# model140.net
KiCad netlist of a schematic drawn in EAGLE
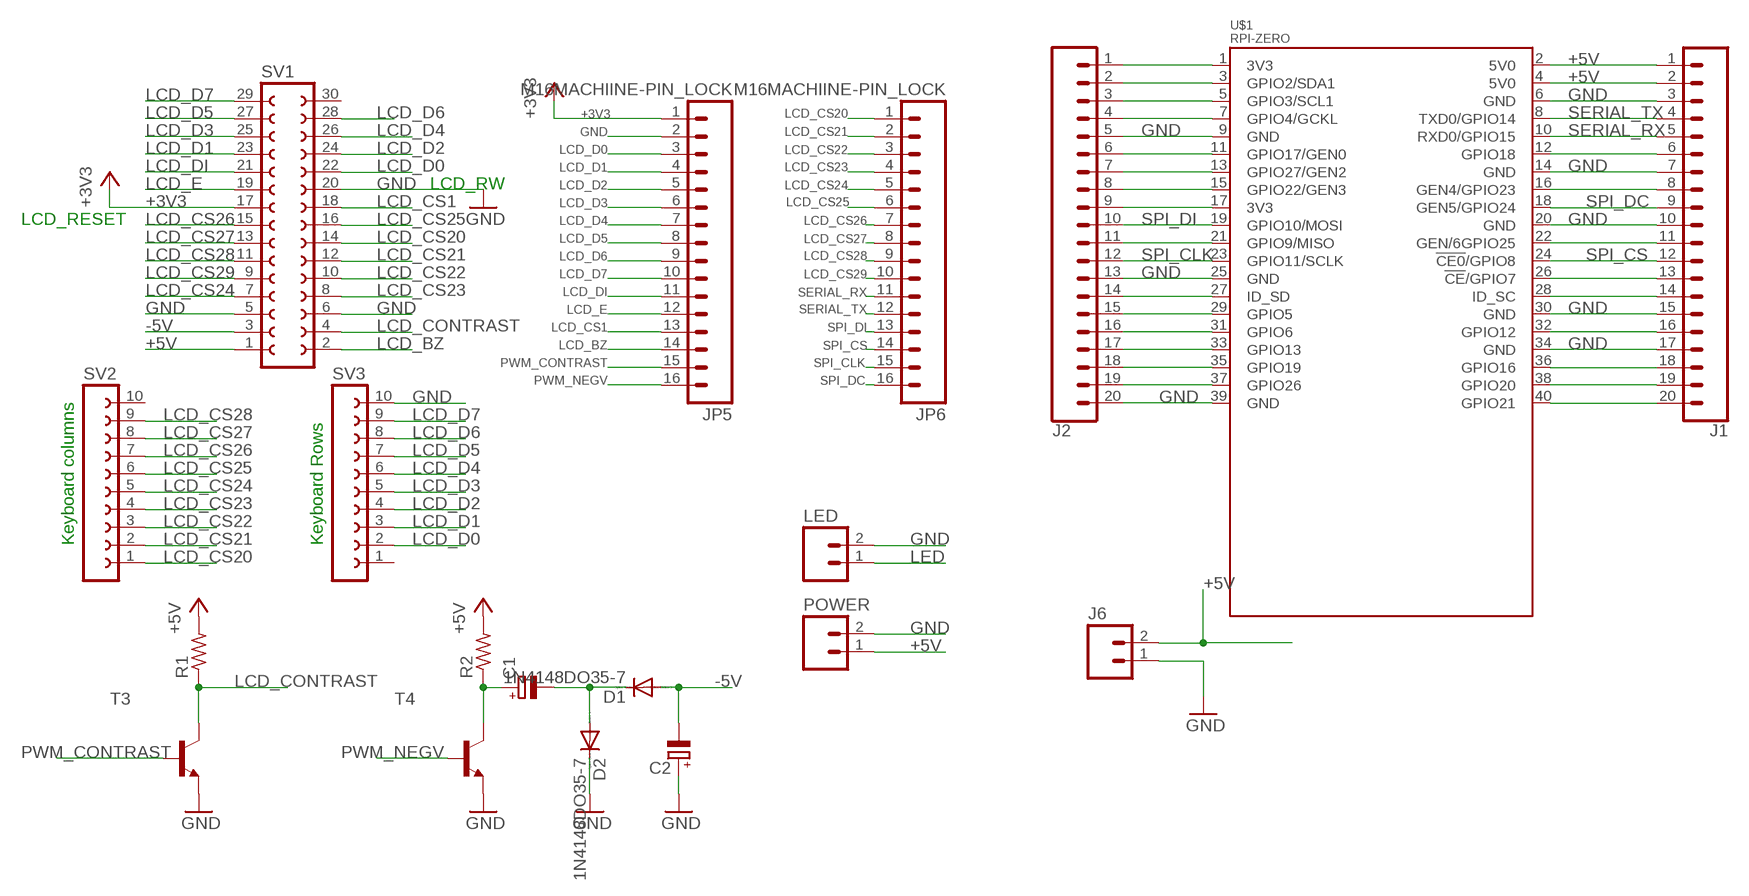
[diagram p0: schematic, sheet 1]

(export (version "E")
  (design (tool "Eeschema 10.0.6"))
  (components
    (comp (ref "C1")
      (value "CPOL-EUE2.5-7")
      (footprint "eagle-import:E2,5-7")
      (libsource (lib "eagle-import") (part "CPOL-EUE2.5-7"))
    )
    (comp (ref "C2")
      (value "CPOL-EUE2.5-7")
      (footprint "eagle-import:E2,5-7")
      (libsource (lib "eagle-import") (part "CPOL-EUE2.5-7"))
    )
    (comp (ref "D1")
      (value "1N4148DO35-7")
      (footprint "eagle-import:DO35-7")
      (libsource (lib "eagle-import") (part "1N4148DO35-7"))
    )
    (comp (ref "D2")
      (value "1N4148DO35-7")
      (footprint "eagle-import:DO35-7")
      (libsource (lib "eagle-import") (part "1N4148DO35-7"))
    )
    (comp (ref "J1")
      (value "CONN_20")
      (footprint "eagle-import:1X20")
      (libsource (lib "eagle-import") (part "CONN_20"))
    )
    (comp (ref "J2")
      (value "CONN_20")
      (footprint "eagle-import:1X20")
      (libsource (lib "eagle-import") (part "CONN_20"))
    )
    (comp (ref "J6")
      (value "M02PTH")
      (footprint "eagle-import:1X02")
      (libsource (lib "eagle-import") (part "M02PTH"))
    )
    (comp (ref "JP5")
      (value "M16MACHIINE-PIN_LOCK")
      (footprint "eagle-import:1X16_MACHINE-PIN-HEADER_LOCK.004@1")
      (libsource (lib "eagle-import") (part "M16MACHIINE-PIN_LOCK"))
    )
    (comp (ref "JP6")
      (value "M16MACHIINE-PIN_LOCK")
      (footprint "eagle-import:1X16_MACHINE-PIN-HEADER_LOCK.004@1")
      (libsource (lib "eagle-import") (part "M16MACHIINE-PIN_LOCK"))
    )
    (comp (ref "LED")
      (value "M02PTH")
      (footprint "eagle-import:1X02")
      (libsource (lib "eagle-import") (part "M02PTH"))
    )
    (comp (ref "POWER")
      (value "M02PTH")
      (footprint "eagle-import:1X02")
      (libsource (lib "eagle-import") (part "M02PTH"))
    )
    (comp (ref "R1")
      (value "R-US_0204/5")
      (footprint "eagle-import:0204_5")
      (libsource (lib "eagle-import") (part "R-US_0204/5"))
    )
    (comp (ref "R2")
      (value "R-US_0204/5")
      (footprint "eagle-import:0204_5")
      (libsource (lib "eagle-import") (part "R-US_0204/5"))
    )
    (comp (ref "SV1")
      (value "FE15-2")
      (footprint "eagle-import:FE15-2")
      (libsource (lib "eagle-import") (part "FE15-2"))
    )
    (comp (ref "SV2")
      (value "FE10W")
      (footprint "eagle-import:FE10W")
      (libsource (lib "eagle-import") (part "FE10W"))
    )
    (comp (ref "SV3")
      (value "FE10W")
      (footprint "eagle-import:FE10W")
      (libsource (lib "eagle-import") (part "FE10W"))
    )
    (comp (ref "T3")
      (value "MPS2222A-NPN-TO92-CBE")
      (footprint "eagle-import:TO92-CBE")
      (libsource (lib "eagle-import") (part "-NPN-TO92-CBEMPS2222A"))
    )
    (comp (ref "T4")
      (value "MPS2222A-NPN-TO92-CBE")
      (footprint "eagle-import:TO92-CBE")
      (libsource (lib "eagle-import") (part "-NPN-TO92-CBEMPS2222A"))
    )
    (comp (ref "U$1")
      (value "RPI-ZERO")
      (footprint "eagle-import:RASP_PI_ZERO_BOARD_FULL")
      (libsource (lib "eagle-import") (part "RPI-ZERO"))
    )
  )
  (nets
    (net (code "1") (name "+3V3") (class "Default")
      (node (ref "JP5") (pin "1") (pinfunction "1_1") (pintype "passive"))
      (node (ref "SV1") (pin "17") (pinfunction "17_17") (pintype "passive"))
    )
    (net (code "2") (name "+5V") (class "Default")
      (node (ref "J1") (pin "1") (pinfunction "1_1") (pintype "passive"))
      (node (ref "J1") (pin "2") (pinfunction "2_2") (pintype "passive"))
      (node (ref "J6") (pin "2") (pinfunction "2_2") (pintype "passive"))
      (node (ref "POWER") (pin "1") (pinfunction "1_1") (pintype "passive"))
      (node (ref "R1") (pin "2") (pinfunction "2_2") (pintype "passive"))
      (node (ref "R2") (pin "2") (pinfunction "2_2") (pintype "passive"))
      (node (ref "SV1") (pin "1") (pinfunction "1_1") (pintype "passive"))
      (node (ref "U$1") (pin "2") (pinfunction "5V0_2") (pintype "power_in"))
      (node (ref "U$1") (pin "4") (pinfunction "5V0_4") (pintype "power_in"))
    )
    (net (code "3") (name "/-5V") (class "Default")
      (node (ref "C2") (pin "-") (pinfunction "-_-") (pintype "passive"))
      (node (ref "D1") (pin "A") (pinfunction "A_A") (pintype "passive"))
      (node (ref "SV1") (pin "3") (pinfunction "3_3") (pintype "passive"))
    )
    (net (code "4") (name "/LCD_BZ") (class "Default")
      (node (ref "JP5") (pin "14") (pinfunction "14_14") (pintype "passive"))
      (node (ref "SV1") (pin "2") (pinfunction "2_2") (pintype "passive"))
    )
    (net (code "5") (name "/LCD_CONTRAST") (class "Default")
      (node (ref "R1") (pin "1") (pinfunction "1_1") (pintype "passive"))
      (node (ref "SV1") (pin "4") (pinfunction "4_4") (pintype "passive"))
      (node (ref "T3") (pin "C") (pinfunction "C_C") (pintype "passive"))
    )
    (net (code "6") (name "/LCD_CS1") (class "Default")
      (node (ref "JP5") (pin "13") (pinfunction "13_13") (pintype "passive"))
      (node (ref "SV1") (pin "18") (pinfunction "18_18") (pintype "passive"))
    )
    (net (code "7") (name "/LCD_CS20") (class "Default")
      (node (ref "JP6") (pin "1") (pinfunction "1_1") (pintype "passive"))
      (node (ref "SV1") (pin "14") (pinfunction "14_14") (pintype "passive"))
      (node (ref "SV2") (pin "1") (pinfunction "1_1") (pintype "passive"))
    )
    (net (code "8") (name "/LCD_CS21") (class "Default")
      (node (ref "JP6") (pin "2") (pinfunction "2_2") (pintype "passive"))
      (node (ref "SV1") (pin "12") (pinfunction "12_12") (pintype "passive"))
      (node (ref "SV2") (pin "2") (pinfunction "2_2") (pintype "passive"))
    )
    (net (code "9") (name "/LCD_CS22") (class "Default")
      (node (ref "JP6") (pin "3") (pinfunction "3_3") (pintype "passive"))
      (node (ref "SV1") (pin "10") (pinfunction "10_10") (pintype "passive"))
      (node (ref "SV2") (pin "3") (pinfunction "3_3") (pintype "passive"))
    )
    (net (code "10") (name "/LCD_CS23") (class "Default")
      (node (ref "JP6") (pin "4") (pinfunction "4_4") (pintype "passive"))
      (node (ref "SV1") (pin "8") (pinfunction "8_8") (pintype "passive"))
      (node (ref "SV2") (pin "4") (pinfunction "4_4") (pintype "passive"))
    )
    (net (code "11") (name "/LCD_CS24") (class "Default")
      (node (ref "JP6") (pin "5") (pinfunction "5_5") (pintype "passive"))
      (node (ref "SV1") (pin "7") (pinfunction "7_7") (pintype "passive"))
      (node (ref "SV2") (pin "5") (pinfunction "5_5") (pintype "passive"))
    )
    (net (code "12") (name "/LCD_CS25") (class "Default")
      (node (ref "JP6") (pin "6") (pinfunction "6_6") (pintype "passive"))
      (node (ref "SV1") (pin "16") (pinfunction "16_16") (pintype "passive"))
      (node (ref "SV2") (pin "6") (pinfunction "6_6") (pintype "passive"))
    )
    (net (code "13") (name "/LCD_CS26") (class "Default")
      (node (ref "JP6") (pin "7") (pinfunction "7_7") (pintype "passive"))
      (node (ref "SV1") (pin "15") (pinfunction "15_15") (pintype "passive"))
      (node (ref "SV2") (pin "7") (pinfunction "7_7") (pintype "passive"))
    )
    (net (code "14") (name "/LCD_CS27") (class "Default")
      (node (ref "JP6") (pin "8") (pinfunction "8_8") (pintype "passive"))
      (node (ref "SV1") (pin "13") (pinfunction "13_13") (pintype "passive"))
      (node (ref "SV2") (pin "8") (pinfunction "8_8") (pintype "passive"))
    )
    (net (code "15") (name "/LCD_CS28") (class "Default")
      (node (ref "JP6") (pin "9") (pinfunction "9_9") (pintype "passive"))
      (node (ref "SV1") (pin "11") (pinfunction "11_11") (pintype "passive"))
      (node (ref "SV2") (pin "9") (pinfunction "9_9") (pintype "passive"))
    )
    (net (code "16") (name "/LCD_CS29") (class "Default")
      (node (ref "JP6") (pin "10") (pinfunction "10_10") (pintype "passive"))
      (node (ref "SV1") (pin "9") (pinfunction "9_9") (pintype "passive"))
    )
    (net (code "17") (name "/LCD_D0") (class "Default")
      (node (ref "JP5") (pin "3") (pinfunction "3_3") (pintype "passive"))
      (node (ref "SV1") (pin "22") (pinfunction "22_22") (pintype "passive"))
      (node (ref "SV3") (pin "2") (pinfunction "2_2") (pintype "passive"))
    )
    (net (code "18") (name "/LCD_D1") (class "Default")
      (node (ref "JP5") (pin "4") (pinfunction "4_4") (pintype "passive"))
      (node (ref "SV1") (pin "23") (pinfunction "23_23") (pintype "passive"))
      (node (ref "SV3") (pin "3") (pinfunction "3_3") (pintype "passive"))
    )
    (net (code "19") (name "/LCD_D2") (class "Default")
      (node (ref "JP5") (pin "5") (pinfunction "5_5") (pintype "passive"))
      (node (ref "SV1") (pin "24") (pinfunction "24_24") (pintype "passive"))
      (node (ref "SV3") (pin "4") (pinfunction "4_4") (pintype "passive"))
    )
    (net (code "20") (name "/LCD_D3") (class "Default")
      (node (ref "JP5") (pin "6") (pinfunction "6_6") (pintype "passive"))
      (node (ref "SV1") (pin "25") (pinfunction "25_25") (pintype "passive"))
      (node (ref "SV3") (pin "5") (pinfunction "5_5") (pintype "passive"))
    )
    (net (code "21") (name "/LCD_D4") (class "Default")
      (node (ref "JP5") (pin "7") (pinfunction "7_7") (pintype "passive"))
      (node (ref "SV1") (pin "26") (pinfunction "26_26") (pintype "passive"))
      (node (ref "SV3") (pin "6") (pinfunction "6_6") (pintype "passive"))
    )
    (net (code "22") (name "/LCD_D5") (class "Default")
      (node (ref "JP5") (pin "8") (pinfunction "8_8") (pintype "passive"))
      (node (ref "SV1") (pin "27") (pinfunction "27_27") (pintype "passive"))
      (node (ref "SV3") (pin "7") (pinfunction "7_7") (pintype "passive"))
    )
    (net (code "23") (name "/LCD_D6") (class "Default")
      (node (ref "JP5") (pin "9") (pinfunction "9_9") (pintype "passive"))
      (node (ref "SV1") (pin "28") (pinfunction "28_28") (pintype "passive"))
      (node (ref "SV3") (pin "8") (pinfunction "8_8") (pintype "passive"))
    )
    (net (code "24") (name "/LCD_D7") (class "Default")
      (node (ref "JP5") (pin "10") (pinfunction "10_10") (pintype "passive"))
      (node (ref "SV1") (pin "29") (pinfunction "29_29") (pintype "passive"))
      (node (ref "SV3") (pin "9") (pinfunction "9_9") (pintype "passive"))
    )
    (net (code "25") (name "/LCD_DI") (class "Default")
      (node (ref "JP5") (pin "11") (pinfunction "11_11") (pintype "passive"))
      (node (ref "SV1") (pin "21") (pinfunction "21_21") (pintype "passive"))
    )
    (net (code "26") (name "/LCD_E") (class "Default")
      (node (ref "JP5") (pin "12") (pinfunction "12_12") (pintype "passive"))
      (node (ref "SV1") (pin "19") (pinfunction "19_19") (pintype "passive"))
    )
    (net (code "27") (name "/LED") (class "Default")
      (node (ref "LED") (pin "1") (pinfunction "1_1") (pintype "passive"))
    )
    (net (code "28") (name "/PWM_CONTRAST") (class "Default")
      (node (ref "JP5") (pin "15") (pinfunction "15_15") (pintype "passive"))
      (node (ref "T3") (pin "B") (pinfunction "B_B") (pintype "passive"))
    )
    (net (code "29") (name "/PWM_NEGV") (class "Default")
      (node (ref "JP5") (pin "16") (pinfunction "16_16") (pintype "passive"))
      (node (ref "T4") (pin "B") (pinfunction "B_B") (pintype "passive"))
    )
    (net (code "30") (name "/SERIAL_RX") (class "Default")
      (node (ref "J1") (pin "5") (pinfunction "5_5") (pintype "passive"))
      (node (ref "JP6") (pin "11") (pinfunction "11_11") (pintype "passive"))
      (node (ref "U$1") (pin "10") (pinfunction "RXD0/GPIO15_10") (pintype "bidirectional"))
    )
    (net (code "31") (name "/SERIAL_TX") (class "Default")
      (node (ref "J1") (pin "4") (pinfunction "4_4") (pintype "passive"))
      (node (ref "JP6") (pin "12") (pinfunction "12_12") (pintype "passive"))
      (node (ref "U$1") (pin "8") (pinfunction "TXD0/GPIO14_8") (pintype "bidirectional"))
    )
    (net (code "32") (name "/SPI_CLK") (class "Default")
      (node (ref "J2") (pin "12") (pinfunction "12_12") (pintype "passive"))
      (node (ref "JP6") (pin "15") (pinfunction "15_15") (pintype "passive"))
      (node (ref "U$1") (pin "23") (pinfunction "GPIO11/SCLK_23") (pintype "bidirectional"))
    )
    (net (code "33") (name "/SPI_CS") (class "Default")
      (node (ref "J1") (pin "12") (pinfunction "12_12") (pintype "passive"))
      (node (ref "JP6") (pin "14") (pinfunction "14_14") (pintype "passive"))
      (node (ref "U$1") (pin "24") (pinfunction "~{CE0}/GPIO8_24") (pintype "bidirectional"))
    )
    (net (code "34") (name "/SPI_DC") (class "Default")
      (node (ref "J1") (pin "9") (pinfunction "9_9") (pintype "passive"))
      (node (ref "JP6") (pin "16") (pinfunction "16_16") (pintype "passive"))
      (node (ref "U$1") (pin "18") (pinfunction "GEN5/GPIO24_18") (pintype "bidirectional"))
    )
    (net (code "35") (name "/SPI_DI") (class "Default")
      (node (ref "J2") (pin "10") (pinfunction "10_10") (pintype "passive"))
      (node (ref "JP6") (pin "13") (pinfunction "13_13") (pintype "passive"))
      (node (ref "U$1") (pin "19") (pinfunction "GPIO10/MOSI_19") (pintype "bidirectional"))
    )
    (net (code "36") (name "GND") (class "Default")
      (node (ref "C2") (pin "+") (pinfunction "+_+") (pintype "passive"))
      (node (ref "D2") (pin "C") (pinfunction "C_C") (pintype "passive"))
      (node (ref "J1") (pin "10") (pinfunction "10_10") (pintype "passive"))
      (node (ref "J1") (pin "15") (pinfunction "15_15") (pintype "passive"))
      (node (ref "J1") (pin "17") (pinfunction "17_17") (pintype "passive"))
      (node (ref "J1") (pin "3") (pinfunction "3_3") (pintype "passive"))
      (node (ref "J1") (pin "7") (pinfunction "7_7") (pintype "passive"))
      (node (ref "J2") (pin "13") (pinfunction "13_13") (pintype "passive"))
      (node (ref "J2") (pin "20") (pinfunction "20_20") (pintype "passive"))
      (node (ref "J2") (pin "5") (pinfunction "5_5") (pintype "passive"))
      (node (ref "J6") (pin "1") (pinfunction "1_1") (pintype "passive"))
      (node (ref "JP5") (pin "2") (pinfunction "2_2") (pintype "passive"))
      (node (ref "LED") (pin "2") (pinfunction "2_2") (pintype "passive"))
      (node (ref "POWER") (pin "2") (pinfunction "2_2") (pintype "passive"))
      (node (ref "SV1") (pin "20") (pinfunction "20_20") (pintype "passive"))
      (node (ref "SV1") (pin "5") (pinfunction "5_5") (pintype "passive"))
      (node (ref "SV1") (pin "6") (pinfunction "6_6") (pintype "passive"))
      (node (ref "SV3") (pin "10") (pinfunction "10_10") (pintype "passive"))
      (node (ref "T3") (pin "E") (pinfunction "E_E") (pintype "passive"))
      (node (ref "T4") (pin "E") (pinfunction "E_E") (pintype "passive"))
      (node (ref "U$1") (pin "14") (pinfunction "GND_14") (pintype "power_in"))
      (node (ref "U$1") (pin "20") (pinfunction "GND_20") (pintype "power_in"))
      (node (ref "U$1") (pin "25") (pinfunction "GND_25") (pintype "power_in"))
      (node (ref "U$1") (pin "30") (pinfunction "GND_30") (pintype "power_in"))
      (node (ref "U$1") (pin "34") (pinfunction "GND_34") (pintype "power_in"))
      (node (ref "U$1") (pin "39") (pinfunction "GND_39") (pintype "power_in"))
      (node (ref "U$1") (pin "6") (pinfunction "GND_6") (pintype "power_in"))
      (node (ref "U$1") (pin "9") (pinfunction "GND_9") (pintype "power_in"))
    )
    (net (code "37") (name "Net-(C1-Pad+)") (class "Default")
      (node (ref "C1") (pin "+") (pinfunction "+_+") (pintype "passive"))
      (node (ref "R2") (pin "1") (pinfunction "1_1") (pintype "passive"))
      (node (ref "T4") (pin "C") (pinfunction "C_C") (pintype "passive"))
    )
    (net (code "38") (name "Net-(C1-Pad-)") (class "Default")
      (node (ref "C1") (pin "-") (pinfunction "-_-") (pintype "passive"))
      (node (ref "D1") (pin "C") (pinfunction "C_C") (pintype "passive"))
      (node (ref "D2") (pin "A") (pinfunction "A_A") (pintype "passive"))
    )
    (net (code "39") (name "Net-(J2-Pad1)") (class "Default")
      (node (ref "J2") (pin "1") (pinfunction "1_1") (pintype "passive"))
      (node (ref "U$1") (pin "1") (pinfunction "3V3_1") (pintype "power_in"))
    )
    (net (code "40") (name "Net-(J2-Pad9)") (class "Default")
      (node (ref "J2") (pin "9") (pinfunction "9_9") (pintype "passive"))
      (node (ref "U$1") (pin "17") (pinfunction "3V3_17") (pintype "power_in"))
    )
    (net (code "41") (name "Net-(U$1-GEN4{slash}GPIO23)") (class "Default")
      (node (ref "J1") (pin "8") (pinfunction "8_8") (pintype "passive"))
      (node (ref "U$1") (pin "16") (pinfunction "GEN4/GPIO23_16") (pintype "bidirectional"))
    )
    (net (code "42") (name "Net-(U$1-GEN{slash}6GPIO25)") (class "Default")
      (node (ref "J1") (pin "11") (pinfunction "11_11") (pintype "passive"))
      (node (ref "U$1") (pin "22") (pinfunction "GEN/6GPIO25_22") (pintype "bidirectional"))
    )
    (net (code "43") (name "Net-(U$1-GPIO2{slash}SDA1)") (class "Default")
      (node (ref "J2") (pin "2") (pinfunction "2_2") (pintype "passive"))
      (node (ref "U$1") (pin "3") (pinfunction "GPIO2/SDA1_3") (pintype "bidirectional"))
    )
    (net (code "44") (name "Net-(U$1-GPIO3{slash}SCL1)") (class "Default")
      (node (ref "J2") (pin "3") (pinfunction "3_3") (pintype "passive"))
      (node (ref "U$1") (pin "5") (pinfunction "GPIO3/SCL1_5") (pintype "bidirectional"))
    )
    (net (code "45") (name "Net-(U$1-GPIO4{slash}GCKL)") (class "Default")
      (node (ref "J2") (pin "4") (pinfunction "4_4") (pintype "passive"))
      (node (ref "U$1") (pin "7") (pinfunction "GPIO4/GCKL_7") (pintype "bidirectional"))
    )
    (net (code "46") (name "Net-(U$1-GPIO5)") (class "Default")
      (node (ref "J2") (pin "15") (pinfunction "15_15") (pintype "passive"))
      (node (ref "U$1") (pin "29") (pinfunction "GPIO5_29") (pintype "bidirectional"))
    )
    (net (code "47") (name "Net-(U$1-GPIO6)") (class "Default")
      (node (ref "J2") (pin "16") (pinfunction "16_16") (pintype "passive"))
      (node (ref "U$1") (pin "31") (pinfunction "GPIO6_31") (pintype "bidirectional"))
    )
    (net (code "48") (name "Net-(U$1-GPIO9{slash}MISO)") (class "Default")
      (node (ref "J2") (pin "11") (pinfunction "11_11") (pintype "passive"))
      (node (ref "U$1") (pin "21") (pinfunction "GPIO9/MISO_21") (pintype "bidirectional"))
    )
    (net (code "49") (name "Net-(U$1-GPIO12)") (class "Default")
      (node (ref "J1") (pin "16") (pinfunction "16_16") (pintype "passive"))
      (node (ref "U$1") (pin "32") (pinfunction "GPIO12_32") (pintype "bidirectional"))
    )
    (net (code "50") (name "Net-(U$1-GPIO13)") (class "Default")
      (node (ref "J2") (pin "17") (pinfunction "17_17") (pintype "passive"))
      (node (ref "U$1") (pin "33") (pinfunction "GPIO13_33") (pintype "bidirectional"))
    )
    (net (code "51") (name "Net-(U$1-GPIO16)") (class "Default")
      (node (ref "J1") (pin "18") (pinfunction "18_18") (pintype "passive"))
      (node (ref "U$1") (pin "36") (pinfunction "GPIO16_36") (pintype "bidirectional"))
    )
    (net (code "52") (name "Net-(U$1-GPIO17{slash}GEN0)") (class "Default")
      (node (ref "J2") (pin "6") (pinfunction "6_6") (pintype "passive"))
      (node (ref "U$1") (pin "11") (pinfunction "GPIO17/GEN0_11") (pintype "bidirectional"))
    )
    (net (code "53") (name "Net-(U$1-GPIO18)") (class "Default")
      (node (ref "J1") (pin "6") (pinfunction "6_6") (pintype "passive"))
      (node (ref "U$1") (pin "12") (pinfunction "GPIO18_12") (pintype "bidirectional"))
    )
    (net (code "54") (name "Net-(U$1-GPIO19)") (class "Default")
      (node (ref "J2") (pin "18") (pinfunction "18_18") (pintype "passive"))
      (node (ref "U$1") (pin "35") (pinfunction "GPIO19_35") (pintype "bidirectional"))
    )
    (net (code "55") (name "Net-(U$1-GPIO20)") (class "Default")
      (node (ref "J1") (pin "19") (pinfunction "19_19") (pintype "passive"))
      (node (ref "U$1") (pin "38") (pinfunction "GPIO20_38") (pintype "bidirectional"))
    )
    (net (code "56") (name "Net-(U$1-GPIO21)") (class "Default")
      (node (ref "J1") (pin "20") (pinfunction "20_20") (pintype "passive"))
      (node (ref "U$1") (pin "40") (pinfunction "GPIO21_40") (pintype "bidirectional"))
    )
    (net (code "57") (name "Net-(U$1-GPIO22{slash}GEN3)") (class "Default")
      (node (ref "J2") (pin "8") (pinfunction "8_8") (pintype "passive"))
      (node (ref "U$1") (pin "15") (pinfunction "GPIO22/GEN3_15") (pintype "bidirectional"))
    )
    (net (code "58") (name "Net-(U$1-GPIO26)") (class "Default")
      (node (ref "J2") (pin "19") (pinfunction "19_19") (pintype "passive"))
      (node (ref "U$1") (pin "37") (pinfunction "GPIO26_37") (pintype "bidirectional"))
    )
    (net (code "59") (name "Net-(U$1-GPIO27{slash}GEN2)") (class "Default")
      (node (ref "J2") (pin "7") (pinfunction "7_7") (pintype "passive"))
      (node (ref "U$1") (pin "13") (pinfunction "GPIO27/GEN2_13") (pintype "bidirectional"))
    )
    (net (code "60") (name "Net-(U$1-ID_SC)") (class "Default")
      (node (ref "J1") (pin "14") (pinfunction "14_14") (pintype "passive"))
      (node (ref "U$1") (pin "28") (pinfunction "ID_SC_28") (pintype "bidirectional"))
    )
    (net (code "61") (name "Net-(U$1-ID_SD)") (class "Default")
      (node (ref "J2") (pin "14") (pinfunction "14_14") (pintype "passive"))
      (node (ref "U$1") (pin "27") (pinfunction "ID_SD_27") (pintype "bidirectional"))
    )
    (net (code "62") (name "Net-(U$1-~{CE}{slash}GPIO7)") (class "Default")
      (node (ref "J1") (pin "13") (pinfunction "13_13") (pintype "passive"))
      (node (ref "U$1") (pin "26") (pinfunction "~{CE}/GPIO7_26") (pintype "bidirectional"))
    )
    (net (code "63") (name "unconnected-(SV1-Pad30)") (class "Default")
      (node (ref "SV1") (pin "30") (pinfunction "30_30") (pintype "passive"))
    )
    (net (code "64") (name "unconnected-(SV2-Pad10)") (class "Default")
      (node (ref "SV2") (pin "10") (pinfunction "10_10") (pintype "passive"))
    )
    (net (code "65") (name "unconnected-(SV3-Pad1)") (class "Default")
      (node (ref "SV3") (pin "1") (pinfunction "1_1") (pintype "passive"))
    )
  )
)
